# M222B.net
KiCad netlist of a schematic drawn in EAGLE
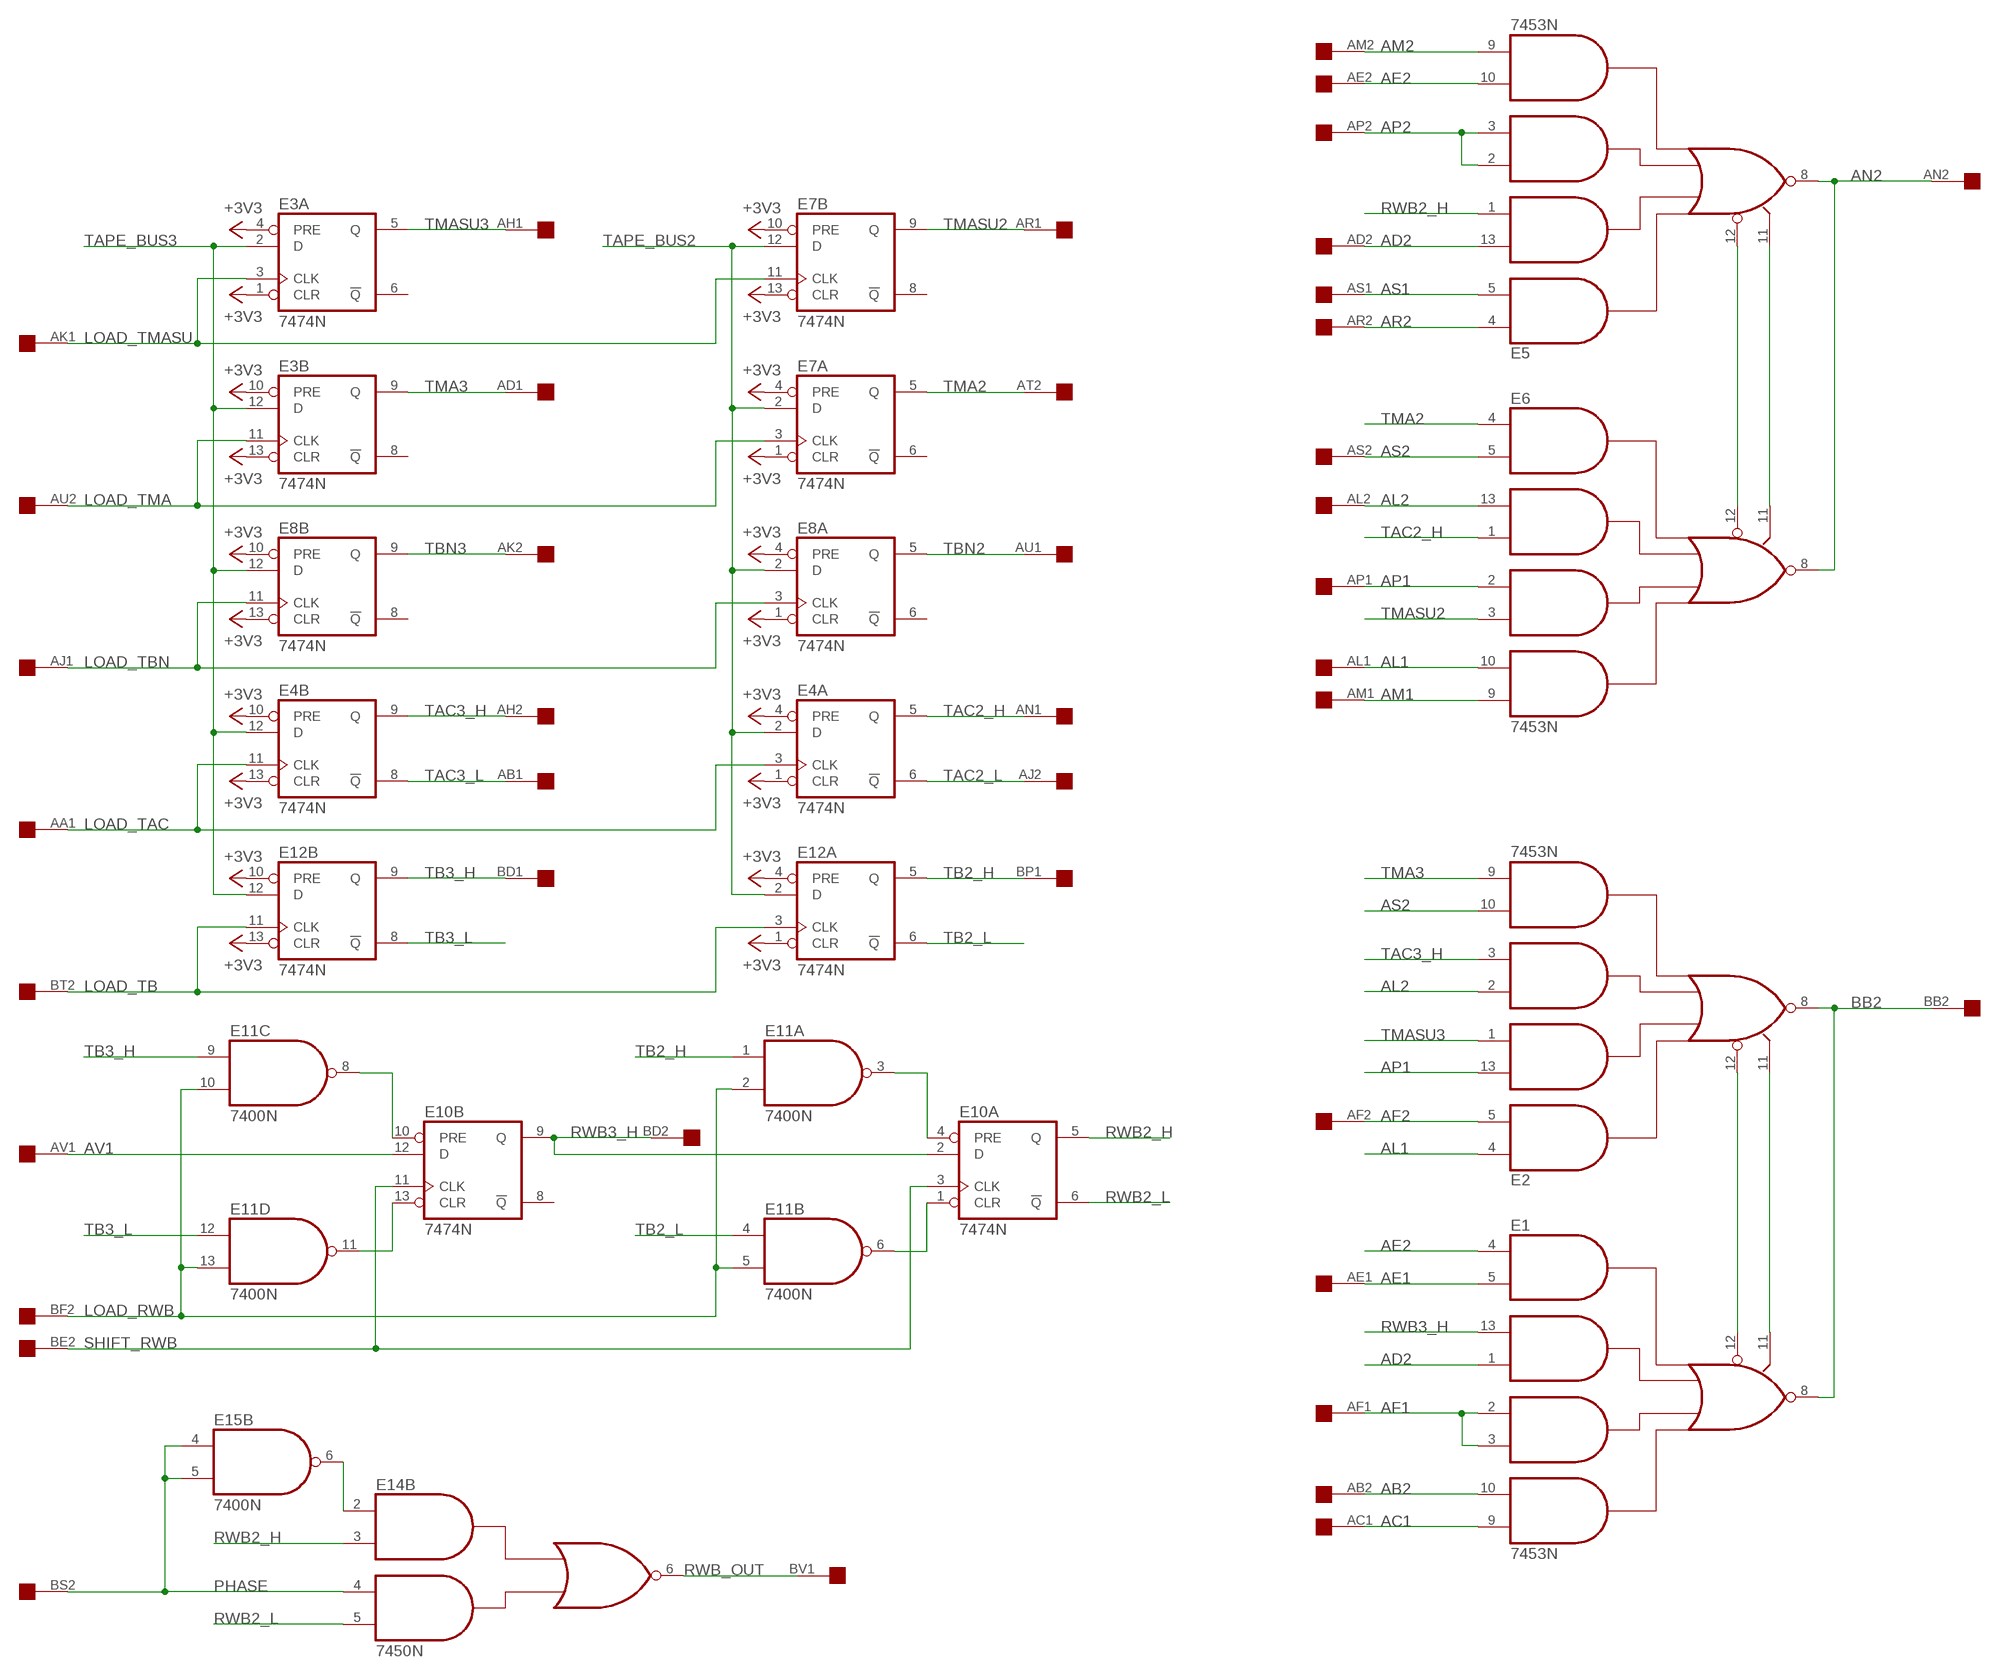
[diagram p0: schematic, sheet 1, part 1 of 2]
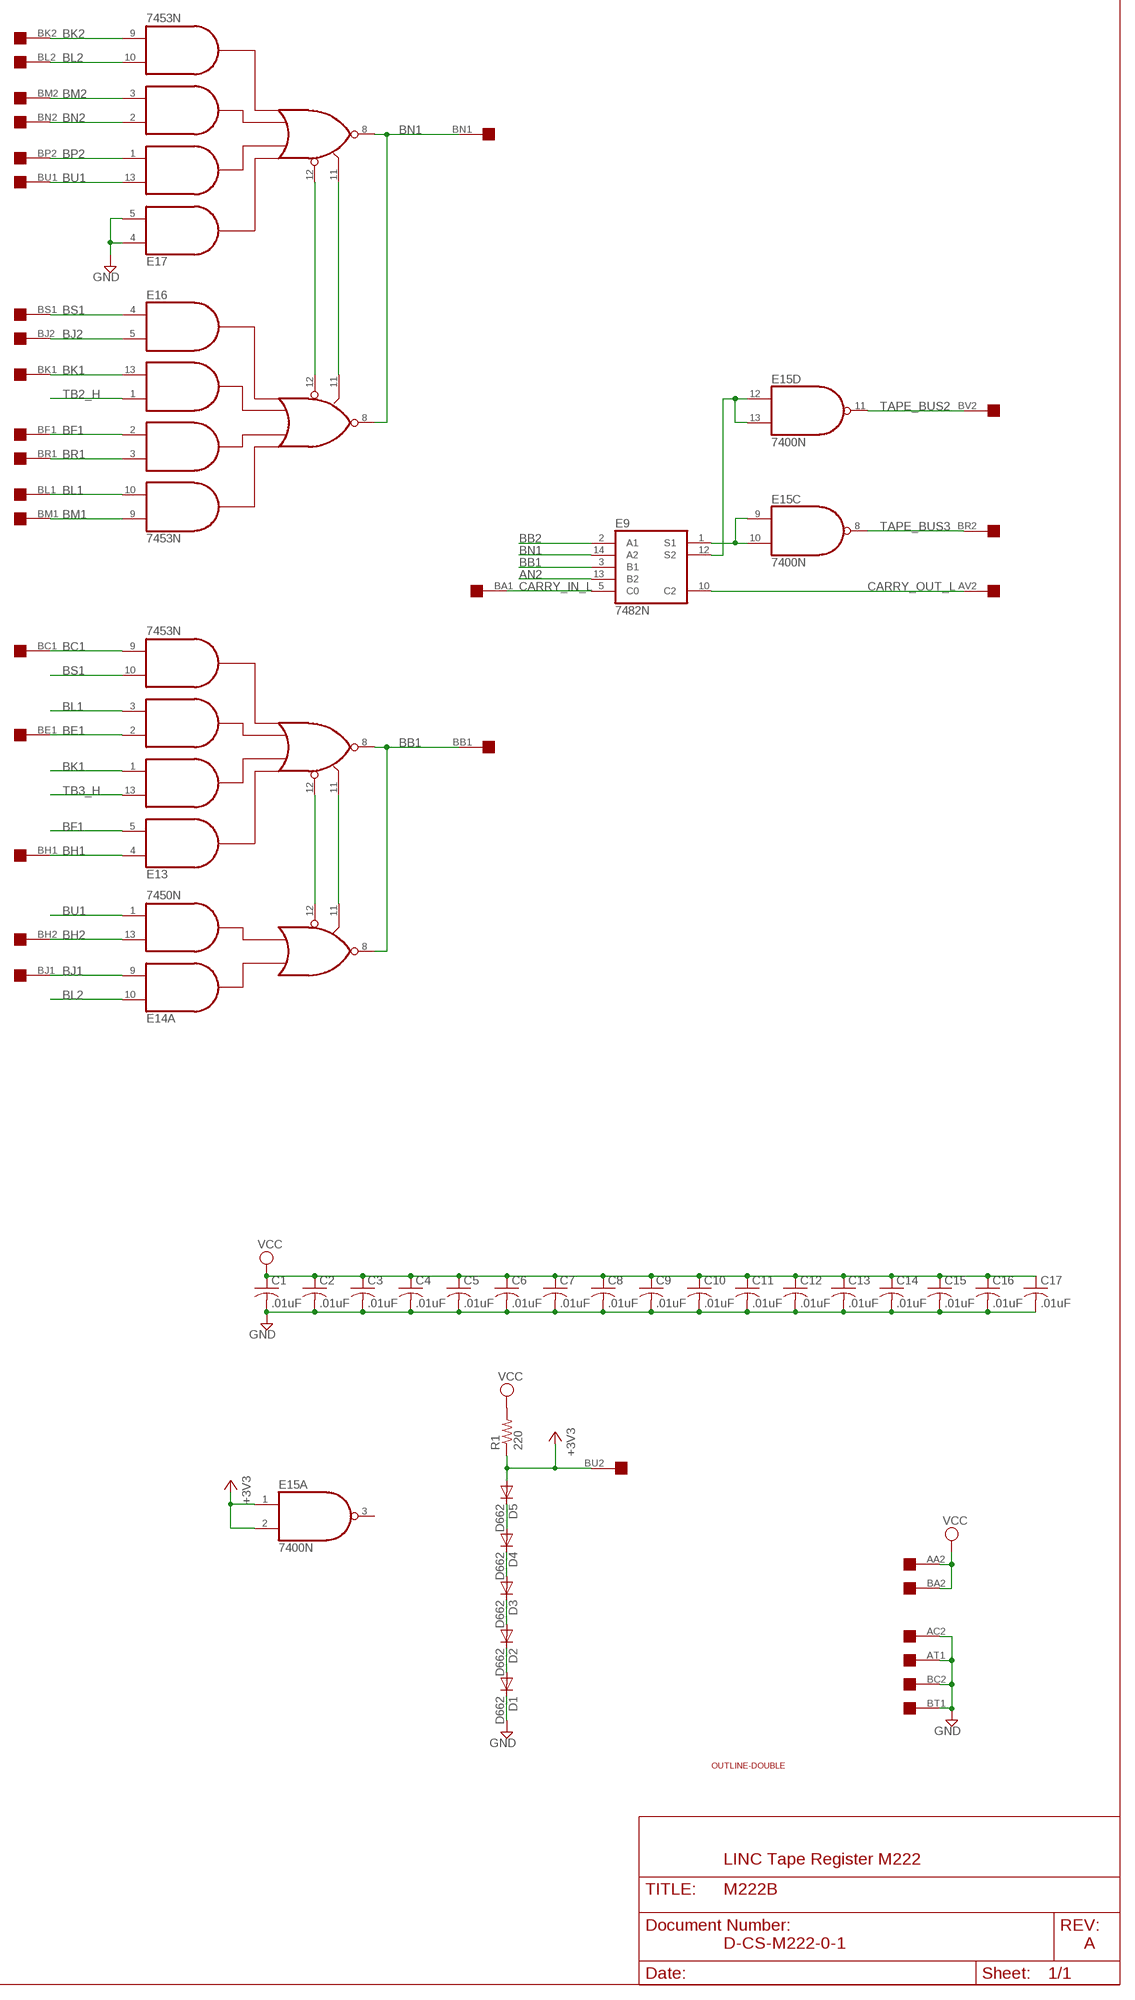
[diagram p1: schematic, sheet 1, part 2 of 2]

(export (version "E")
  (design (tool "Eeschema 10.0.6"))
  (components
    (comp (ref "C1")
      (value ".01uF")
      (footprint "eagle-import:C050-025X075")
      (libsource (lib "eagle-import") (part "C-US050-025X075"))
    )
    (comp (ref "C2")
      (value ".01uF")
      (footprint "eagle-import:C050-025X075")
      (libsource (lib "eagle-import") (part "C-US050-025X075"))
    )
    (comp (ref "C3")
      (value ".01uF")
      (footprint "eagle-import:C050-025X075")
      (libsource (lib "eagle-import") (part "C-US050-025X075"))
    )
    (comp (ref "C4")
      (value ".01uF")
      (footprint "eagle-import:C050-025X075")
      (libsource (lib "eagle-import") (part "C-US050-025X075"))
    )
    (comp (ref "C5")
      (value ".01uF")
      (footprint "eagle-import:C050-025X075")
      (libsource (lib "eagle-import") (part "C-US050-025X075"))
    )
    (comp (ref "C6")
      (value ".01uF")
      (footprint "eagle-import:C050-025X075")
      (libsource (lib "eagle-import") (part "C-US050-025X075"))
    )
    (comp (ref "C7")
      (value ".01uF")
      (footprint "eagle-import:C050-025X075")
      (libsource (lib "eagle-import") (part "C-US050-025X075"))
    )
    (comp (ref "C8")
      (value ".01uF")
      (footprint "eagle-import:C050-025X075")
      (libsource (lib "eagle-import") (part "C-US050-025X075"))
    )
    (comp (ref "C9")
      (value ".01uF")
      (footprint "eagle-import:C050-025X075")
      (libsource (lib "eagle-import") (part "C-US050-025X075"))
    )
    (comp (ref "C10")
      (value ".01uF")
      (footprint "eagle-import:C050-025X075")
      (libsource (lib "eagle-import") (part "C-US050-025X075"))
    )
    (comp (ref "C11")
      (value ".01uF")
      (footprint "eagle-import:C050-025X075")
      (libsource (lib "eagle-import") (part "C-US050-025X075"))
    )
    (comp (ref "C12")
      (value ".01uF")
      (footprint "eagle-import:C050-025X075")
      (libsource (lib "eagle-import") (part "C-US050-025X075"))
    )
    (comp (ref "C13")
      (value ".01uF")
      (footprint "eagle-import:C050-025X075")
      (libsource (lib "eagle-import") (part "C-US050-025X075"))
    )
    (comp (ref "C14")
      (value ".01uF")
      (footprint "eagle-import:C050-025X075")
      (libsource (lib "eagle-import") (part "C-US050-025X075"))
    )
    (comp (ref "C15")
      (value ".01uF")
      (footprint "eagle-import:C050-025X075")
      (libsource (lib "eagle-import") (part "C-US050-025X075"))
    )
    (comp (ref "C16")
      (value ".01uF")
      (footprint "eagle-import:C050-025X075")
      (libsource (lib "eagle-import") (part "C-US050-025X075"))
    )
    (comp (ref "C17")
      (value ".01uF")
      (footprint "eagle-import:C050-025X075")
      (libsource (lib "eagle-import") (part "C-US050-025X075"))
    )
    (comp (ref "D1")
      (value "D662")
      (footprint "eagle-import:DO35-10")
      (libsource (lib "eagle-import") (part "1N4148DO35-10"))
    )
    (comp (ref "D2")
      (value "D662")
      (footprint "eagle-import:DO35-10")
      (libsource (lib "eagle-import") (part "1N4148DO35-10"))
    )
    (comp (ref "D3")
      (value "D662")
      (footprint "eagle-import:DO35-10")
      (libsource (lib "eagle-import") (part "1N4148DO35-10"))
    )
    (comp (ref "D4")
      (value "D662")
      (footprint "eagle-import:DO35-10")
      (libsource (lib "eagle-import") (part "1N4148DO35-10"))
    )
    (comp (ref "D5")
      (value "D662")
      (footprint "eagle-import:DO35-10")
      (libsource (lib "eagle-import") (part "1N4148DO35-10"))
    )
    (comp (ref "E1")
      (value "7453N")
      (footprint "eagle-import:DIL14")
      (libsource (lib "eagle-import") (part "7453N"))
    )
    (comp (ref "E2")
      (value "7453N")
      (footprint "eagle-import:DIL14")
      (libsource (lib "eagle-import") (part "7453N"))
    )
    (comp (ref "E3")
      (value "7474N")
      (footprint "eagle-import:DIL14")
      (libsource (lib "eagle-import") (part "7474NS"))
    )
    (comp (ref "E4")
      (value "7474N")
      (footprint "eagle-import:DIL14")
      (libsource (lib "eagle-import") (part "7474NS"))
    )
    (comp (ref "E5")
      (value "7453N")
      (footprint "eagle-import:DIL14")
      (libsource (lib "eagle-import") (part "7453N"))
    )
    (comp (ref "E6")
      (value "7453N")
      (footprint "eagle-import:DIL14")
      (libsource (lib "eagle-import") (part "7453N"))
    )
    (comp (ref "E7")
      (value "7474N")
      (footprint "eagle-import:DIL14")
      (libsource (lib "eagle-import") (part "7474NS"))
    )
    (comp (ref "E8")
      (value "7474N")
      (footprint "eagle-import:DIL14")
      (libsource (lib "eagle-import") (part "7474NS"))
    )
    (comp (ref "E9")
      (value "7482N")
      (footprint "eagle-import:DIL14")
      (libsource (lib "eagle-import") (part "7482N"))
    )
    (comp (ref "E10")
      (value "7474N")
      (footprint "eagle-import:DIL14")
      (libsource (lib "eagle-import") (part "7474NS"))
    )
    (comp (ref "E11")
      (value "7400N")
      (footprint "eagle-import:DIL14")
      (libsource (lib "eagle-import") (part "7400N"))
    )
    (comp (ref "E12")
      (value "7474N")
      (footprint "eagle-import:DIL14")
      (libsource (lib "eagle-import") (part "7474NS"))
    )
    (comp (ref "E13")
      (value "7453N")
      (footprint "eagle-import:DIL14")
      (libsource (lib "eagle-import") (part "7453N"))
    )
    (comp (ref "E14")
      (value "7450N")
      (footprint "eagle-import:DIL14")
      (libsource (lib "eagle-import") (part "7450N"))
    )
    (comp (ref "E15")
      (value "7400N")
      (footprint "eagle-import:DIL14")
      (libsource (lib "eagle-import") (part "7400N"))
    )
    (comp (ref "E16")
      (value "7453N")
      (footprint "eagle-import:DIL14")
      (libsource (lib "eagle-import") (part "7453N"))
    )
    (comp (ref "E17")
      (value "7453N")
      (footprint "eagle-import:DIL14")
      (libsource (lib "eagle-import") (part "7453N"))
    )
    (comp (ref "R1")
      (value "220")
      (footprint "eagle-import:0207_10")
      (libsource (lib "eagle-import") (part "R-US_0207/10"))
    )
    (comp (ref "U$1")
      (value "DOUBLE")
      (footprint "eagle-import:EDGE-CON4")
      (libsource (lib "eagle-import") (part "DOUBLE"))
    )
    (comp (ref "U$2")
      (value "OUTLINE-DOUBLE")
      (footprint "eagle-import:DOUBLE")
      (libsource (lib "eagle-import") (part "OUTLINE-DOUBLE"))
    )
  )
  (nets
    (net (code "1") (name "+3V3") (class "Default")
      (node (ref "D5") (pin "A") (pinfunction "A_A") (pintype "passive"))
      (node (ref "E12") (pin "1") (pinfunction "CLR_1") (pintype "input"))
      (node (ref "E12") (pin "10") (pinfunction "PRE_10") (pintype "input"))
      (node (ref "E12") (pin "13") (pinfunction "CLR_13") (pintype "input"))
      (node (ref "E12") (pin "4") (pinfunction "PRE_4") (pintype "input"))
      (node (ref "E15") (pin "1") (pinfunction "I0_1") (pintype "input"))
      (node (ref "E15") (pin "2") (pinfunction "I1_2") (pintype "input"))
      (node (ref "E3") (pin "1") (pinfunction "CLR_1") (pintype "input"))
      (node (ref "E3") (pin "10") (pinfunction "PRE_10") (pintype "input"))
      (node (ref "E3") (pin "13") (pinfunction "CLR_13") (pintype "input"))
      (node (ref "E3") (pin "4") (pinfunction "PRE_4") (pintype "input"))
      (node (ref "E4") (pin "1") (pinfunction "CLR_1") (pintype "input"))
      (node (ref "E4") (pin "10") (pinfunction "PRE_10") (pintype "input"))
      (node (ref "E4") (pin "13") (pinfunction "CLR_13") (pintype "input"))
      (node (ref "E4") (pin "4") (pinfunction "PRE_4") (pintype "input"))
      (node (ref "E7") (pin "1") (pinfunction "CLR_1") (pintype "input"))
      (node (ref "E7") (pin "10") (pinfunction "PRE_10") (pintype "input"))
      (node (ref "E7") (pin "13") (pinfunction "CLR_13") (pintype "input"))
      (node (ref "E7") (pin "4") (pinfunction "PRE_4") (pintype "input"))
      (node (ref "E8") (pin "1") (pinfunction "CLR_1") (pintype "input"))
      (node (ref "E8") (pin "10") (pinfunction "PRE_10") (pintype "input"))
      (node (ref "E8") (pin "13") (pinfunction "CLR_13") (pintype "input"))
      (node (ref "E8") (pin "4") (pinfunction "PRE_4") (pintype "input"))
      (node (ref "R1") (pin "1") (pinfunction "1_1") (pintype "passive"))
      (node (ref "U$1") (pin "BU2") (pinfunction "1_BU2") (pintype "bidirectional"))
    )
    (net (code "2") (name "/AB2") (class "Default")
      (node (ref "E1") (pin "10") (pinfunction "I7_10") (pintype "input"))
      (node (ref "U$1") (pin "AB2") (pinfunction "1_AB2") (pintype "bidirectional"))
    )
    (net (code "3") (name "/AC1") (class "Default")
      (node (ref "E1") (pin "9") (pinfunction "I8_9") (pintype "input"))
      (node (ref "U$1") (pin "AC1") (pinfunction "1_AC1") (pintype "bidirectional"))
    )
    (net (code "4") (name "/AD2") (class "Default")
      (node (ref "E1") (pin "1") (pinfunction "I4_1") (pintype "input"))
      (node (ref "E5") (pin "13") (pinfunction "I3_13") (pintype "input"))
      (node (ref "U$1") (pin "AD2") (pinfunction "1_AD2") (pintype "bidirectional"))
    )
    (net (code "5") (name "/AE1") (class "Default")
      (node (ref "E1") (pin "5") (pinfunction "I2_5") (pintype "input"))
      (node (ref "U$1") (pin "AE1") (pinfunction "1_AE1") (pintype "bidirectional"))
    )
    (net (code "6") (name "/AE2") (class "Default")
      (node (ref "E1") (pin "4") (pinfunction "I1_4") (pintype "input"))
      (node (ref "E5") (pin "10") (pinfunction "I7_10") (pintype "input"))
      (node (ref "U$1") (pin "AE2") (pinfunction "1_AE2") (pintype "bidirectional"))
    )
    (net (code "7") (name "/AF1") (class "Default")
      (node (ref "E1") (pin "2") (pinfunction "I5_2") (pintype "input"))
      (node (ref "E1") (pin "3") (pinfunction "I6_3") (pintype "input"))
      (node (ref "U$1") (pin "AF1") (pinfunction "1_AF1") (pintype "bidirectional"))
    )
    (net (code "8") (name "/AF2") (class "Default")
      (node (ref "E2") (pin "5") (pinfunction "I2_5") (pintype "input"))
      (node (ref "U$1") (pin "AF2") (pinfunction "1_AF2") (pintype "bidirectional"))
    )
    (net (code "9") (name "/AL1") (class "Default")
      (node (ref "E2") (pin "4") (pinfunction "I1_4") (pintype "input"))
      (node (ref "E6") (pin "10") (pinfunction "I7_10") (pintype "input"))
      (node (ref "U$1") (pin "AL1") (pinfunction "1_AL1") (pintype "bidirectional"))
    )
    (net (code "10") (name "/AL2") (class "Default")
      (node (ref "E2") (pin "2") (pinfunction "I5_2") (pintype "input"))
      (node (ref "E6") (pin "13") (pinfunction "I3_13") (pintype "input"))
      (node (ref "U$1") (pin "AL2") (pinfunction "1_AL2") (pintype "bidirectional"))
    )
    (net (code "11") (name "/AM1") (class "Default")
      (node (ref "E6") (pin "9") (pinfunction "I8_9") (pintype "input"))
      (node (ref "U$1") (pin "AM1") (pinfunction "1_AM1") (pintype "bidirectional"))
    )
    (net (code "12") (name "/AM2") (class "Default")
      (node (ref "E5") (pin "9") (pinfunction "I8_9") (pintype "input"))
      (node (ref "U$1") (pin "AM2") (pinfunction "1_AM2") (pintype "bidirectional"))
    )
    (net (code "13") (name "/AN2") (class "Default")
      (node (ref "E5") (pin "8") (pinfunction "O_8") (pintype "output"))
      (node (ref "E6") (pin "8") (pinfunction "O_8") (pintype "output"))
      (node (ref "E9") (pin "13") (pinfunction "B2_13") (pintype "input"))
      (node (ref "U$1") (pin "AN2") (pinfunction "1_AN2") (pintype "bidirectional"))
    )
    (net (code "14") (name "/AP1") (class "Default")
      (node (ref "E2") (pin "13") (pinfunction "I3_13") (pintype "input"))
      (node (ref "E6") (pin "2") (pinfunction "I5_2") (pintype "input"))
      (node (ref "U$1") (pin "AP1") (pinfunction "1_AP1") (pintype "bidirectional"))
    )
    (net (code "15") (name "/AP2") (class "Default")
      (node (ref "E5") (pin "2") (pinfunction "I5_2") (pintype "input"))
      (node (ref "E5") (pin "3") (pinfunction "I6_3") (pintype "input"))
      (node (ref "U$1") (pin "AP2") (pinfunction "1_AP2") (pintype "bidirectional"))
    )
    (net (code "16") (name "/AR2") (class "Default")
      (node (ref "E5") (pin "4") (pinfunction "I1_4") (pintype "input"))
      (node (ref "U$1") (pin "AR2") (pinfunction "1_AR2") (pintype "bidirectional"))
    )
    (net (code "17") (name "/AS1") (class "Default")
      (node (ref "E5") (pin "5") (pinfunction "I2_5") (pintype "input"))
      (node (ref "U$1") (pin "AS1") (pinfunction "1_AS1") (pintype "bidirectional"))
    )
    (net (code "18") (name "/AS2") (class "Default")
      (node (ref "E2") (pin "10") (pinfunction "I7_10") (pintype "input"))
      (node (ref "E6") (pin "5") (pinfunction "I2_5") (pintype "input"))
      (node (ref "U$1") (pin "AS2") (pinfunction "1_AS2") (pintype "bidirectional"))
    )
    (net (code "19") (name "/AV1") (class "Default")
      (node (ref "E10") (pin "12") (pinfunction "D_12") (pintype "input"))
      (node (ref "U$1") (pin "AV1") (pinfunction "1_AV1") (pintype "bidirectional"))
    )
    (net (code "20") (name "/BB1") (class "Default")
      (node (ref "E13") (pin "8") (pinfunction "O_8") (pintype "output"))
      (node (ref "E14") (pin "8") (pinfunction "O_8") (pintype "output"))
      (node (ref "E9") (pin "3") (pinfunction "B1_3") (pintype "input"))
      (node (ref "U$1") (pin "BB1") (pinfunction "1_BB1") (pintype "bidirectional"))
    )
    (net (code "21") (name "/BB2") (class "Default")
      (node (ref "E1") (pin "8") (pinfunction "O_8") (pintype "output"))
      (node (ref "E2") (pin "8") (pinfunction "O_8") (pintype "output"))
      (node (ref "E9") (pin "2") (pinfunction "A1_2") (pintype "input"))
      (node (ref "U$1") (pin "BB2") (pinfunction "1_BB2") (pintype "bidirectional"))
    )
    (net (code "22") (name "/BC1") (class "Default")
      (node (ref "E13") (pin "9") (pinfunction "I8_9") (pintype "input"))
      (node (ref "U$1") (pin "BC1") (pinfunction "1_BC1") (pintype "bidirectional"))
    )
    (net (code "23") (name "/BE1") (class "Default")
      (node (ref "E13") (pin "2") (pinfunction "I5_2") (pintype "input"))
      (node (ref "U$1") (pin "BE1") (pinfunction "1_BE1") (pintype "bidirectional"))
    )
    (net (code "24") (name "/BF1") (class "Default")
      (node (ref "E13") (pin "5") (pinfunction "I2_5") (pintype "input"))
      (node (ref "E16") (pin "2") (pinfunction "I5_2") (pintype "input"))
      (node (ref "U$1") (pin "BF1") (pinfunction "1_BF1") (pintype "bidirectional"))
    )
    (net (code "25") (name "/BH1") (class "Default")
      (node (ref "E13") (pin "4") (pinfunction "I1_4") (pintype "input"))
      (node (ref "U$1") (pin "BH1") (pinfunction "1_BH1") (pintype "bidirectional"))
    )
    (net (code "26") (name "/BH2") (class "Default")
      (node (ref "E14") (pin "13") (pinfunction "I3_13") (pintype "input"))
      (node (ref "U$1") (pin "BH2") (pinfunction "1_BH2") (pintype "bidirectional"))
    )
    (net (code "27") (name "/BJ1") (class "Default")
      (node (ref "E14") (pin "9") (pinfunction "I2_9") (pintype "input"))
      (node (ref "U$1") (pin "BJ1") (pinfunction "1_BJ1") (pintype "bidirectional"))
    )
    (net (code "28") (name "/BJ2") (class "Default")
      (node (ref "E16") (pin "5") (pinfunction "I2_5") (pintype "input"))
      (node (ref "U$1") (pin "BJ2") (pinfunction "1_BJ2") (pintype "bidirectional"))
    )
    (net (code "29") (name "/BK1") (class "Default")
      (node (ref "E13") (pin "1") (pinfunction "I4_1") (pintype "input"))
      (node (ref "E16") (pin "13") (pinfunction "I3_13") (pintype "input"))
      (node (ref "U$1") (pin "BK1") (pinfunction "1_BK1") (pintype "bidirectional"))
    )
    (net (code "30") (name "/BK2") (class "Default")
      (node (ref "E17") (pin "9") (pinfunction "I8_9") (pintype "input"))
      (node (ref "U$1") (pin "BK2") (pinfunction "1_BK2") (pintype "bidirectional"))
    )
    (net (code "31") (name "/BL1") (class "Default")
      (node (ref "E13") (pin "3") (pinfunction "I6_3") (pintype "input"))
      (node (ref "E16") (pin "10") (pinfunction "I7_10") (pintype "input"))
      (node (ref "U$1") (pin "BL1") (pinfunction "1_BL1") (pintype "bidirectional"))
    )
    (net (code "32") (name "/BL2") (class "Default")
      (node (ref "E14") (pin "10") (pinfunction "I1_10") (pintype "input"))
      (node (ref "E17") (pin "10") (pinfunction "I7_10") (pintype "input"))
      (node (ref "U$1") (pin "BL2") (pinfunction "1_BL2") (pintype "bidirectional"))
    )
    (net (code "33") (name "/BM1") (class "Default")
      (node (ref "E16") (pin "9") (pinfunction "I8_9") (pintype "input"))
      (node (ref "U$1") (pin "BM1") (pinfunction "1_BM1") (pintype "bidirectional"))
    )
    (net (code "34") (name "/BM2") (class "Default")
      (node (ref "E17") (pin "3") (pinfunction "I6_3") (pintype "input"))
      (node (ref "U$1") (pin "BM2") (pinfunction "1_BM2") (pintype "bidirectional"))
    )
    (net (code "35") (name "/BN1") (class "Default")
      (node (ref "E16") (pin "8") (pinfunction "O_8") (pintype "output"))
      (node (ref "E17") (pin "8") (pinfunction "O_8") (pintype "output"))
      (node (ref "E9") (pin "14") (pinfunction "A2_14") (pintype "input"))
      (node (ref "U$1") (pin "BN1") (pinfunction "1_BN1") (pintype "bidirectional"))
    )
    (net (code "36") (name "/BN2") (class "Default")
      (node (ref "E17") (pin "2") (pinfunction "I5_2") (pintype "input"))
      (node (ref "U$1") (pin "BN2") (pinfunction "1_BN2") (pintype "bidirectional"))
    )
    (net (code "37") (name "/BP2") (class "Default")
      (node (ref "E17") (pin "1") (pinfunction "I4_1") (pintype "input"))
      (node (ref "U$1") (pin "BP2") (pinfunction "1_BP2") (pintype "bidirectional"))
    )
    (net (code "38") (name "/BR1") (class "Default")
      (node (ref "E16") (pin "3") (pinfunction "I6_3") (pintype "input"))
      (node (ref "U$1") (pin "BR1") (pinfunction "1_BR1") (pintype "bidirectional"))
    )
    (net (code "39") (name "/BS1") (class "Default")
      (node (ref "E13") (pin "10") (pinfunction "I7_10") (pintype "input"))
      (node (ref "E16") (pin "4") (pinfunction "I1_4") (pintype "input"))
      (node (ref "U$1") (pin "BS1") (pinfunction "1_BS1") (pintype "bidirectional"))
    )
    (net (code "40") (name "/BU1") (class "Default")
      (node (ref "E14") (pin "1") (pinfunction "I4_1") (pintype "input"))
      (node (ref "E17") (pin "13") (pinfunction "I3_13") (pintype "input"))
      (node (ref "U$1") (pin "BU1") (pinfunction "1_BU1") (pintype "bidirectional"))
    )
    (net (code "41") (name "/CARRY_IN_L") (class "Default")
      (node (ref "E9") (pin "5") (pinfunction "C0_5") (pintype "input"))
      (node (ref "U$1") (pin "BA1") (pinfunction "1_BA1") (pintype "bidirectional"))
    )
    (net (code "42") (name "/CARRY_OUT_L") (class "Default")
      (node (ref "E9") (pin "10") (pinfunction "C2_10") (pintype "output"))
      (node (ref "U$1") (pin "AV2") (pinfunction "1_AV2") (pintype "bidirectional"))
    )
    (net (code "43") (name "/LOAD_RWB") (class "Default")
      (node (ref "E11") (pin "10") (pinfunction "I1_10") (pintype "input"))
      (node (ref "E11") (pin "13") (pinfunction "I1_13") (pintype "input"))
      (node (ref "E11") (pin "2") (pinfunction "I1_2") (pintype "input"))
      (node (ref "E11") (pin "5") (pinfunction "I1_5") (pintype "input"))
      (node (ref "U$1") (pin "BF2") (pinfunction "1_BF2") (pintype "bidirectional"))
    )
    (net (code "44") (name "/LOAD_TAC") (class "Default")
      (node (ref "E4") (pin "11") (pinfunction "CLK_11") (pintype "input"))
      (node (ref "E4") (pin "3") (pinfunction "CLK_3") (pintype "input"))
      (node (ref "U$1") (pin "AA1") (pinfunction "1_AA1") (pintype "bidirectional"))
    )
    (net (code "45") (name "/LOAD_TB") (class "Default")
      (node (ref "E12") (pin "11") (pinfunction "CLK_11") (pintype "input"))
      (node (ref "E12") (pin "3") (pinfunction "CLK_3") (pintype "input"))
      (node (ref "U$1") (pin "BT2") (pinfunction "1_BT2") (pintype "bidirectional"))
    )
    (net (code "46") (name "/LOAD_TBN") (class "Default")
      (node (ref "E8") (pin "11") (pinfunction "CLK_11") (pintype "input"))
      (node (ref "E8") (pin "3") (pinfunction "CLK_3") (pintype "input"))
      (node (ref "U$1") (pin "AJ1") (pinfunction "1_AJ1") (pintype "bidirectional"))
    )
    (net (code "47") (name "/LOAD_TMA") (class "Default")
      (node (ref "E3") (pin "11") (pinfunction "CLK_11") (pintype "input"))
      (node (ref "E7") (pin "3") (pinfunction "CLK_3") (pintype "input"))
      (node (ref "U$1") (pin "AU2") (pinfunction "1_AU2") (pintype "bidirectional"))
    )
    (net (code "48") (name "/LOAD_TMASU") (class "Default")
      (node (ref "E3") (pin "3") (pinfunction "CLK_3") (pintype "input"))
      (node (ref "E7") (pin "11") (pinfunction "CLK_11") (pintype "input"))
      (node (ref "U$1") (pin "AK1") (pinfunction "1_AK1") (pintype "bidirectional"))
    )
    (net (code "49") (name "/PHASE") (class "Default")
      (node (ref "E14") (pin "4") (pinfunction "I3_4") (pintype "input"))
      (node (ref "E15") (pin "4") (pinfunction "I0_4") (pintype "input"))
      (node (ref "E15") (pin "5") (pinfunction "I1_5") (pintype "input"))
      (node (ref "U$1") (pin "BS2") (pinfunction "1_BS2") (pintype "bidirectional"))
    )
    (net (code "50") (name "/RWB2_H") (class "Default")
      (node (ref "E10") (pin "5") (pinfunction "Q_5") (pintype "output"))
      (node (ref "E14") (pin "3") (pinfunction "I2_3") (pintype "input"))
      (node (ref "E5") (pin "1") (pinfunction "I4_1") (pintype "input"))
    )
    (net (code "51") (name "/RWB2_L") (class "Default")
      (node (ref "E10") (pin "6") (pinfunction "~{Q}_6") (pintype "output"))
      (node (ref "E14") (pin "5") (pinfunction "I4_5") (pintype "input"))
    )
    (net (code "52") (name "/RWB3_H") (class "Default")
      (node (ref "E1") (pin "13") (pinfunction "I3_13") (pintype "input"))
      (node (ref "E10") (pin "2") (pinfunction "D_2") (pintype "input"))
      (node (ref "E10") (pin "9") (pinfunction "Q_9") (pintype "output"))
      (node (ref "U$1") (pin "BD2") (pinfunction "1_BD2") (pintype "bidirectional"))
    )
    (net (code "53") (name "/RWB_OUT") (class "Default")
      (node (ref "E14") (pin "6") (pinfunction "O_6") (pintype "output"))
      (node (ref "U$1") (pin "BV1") (pinfunction "1_BV1") (pintype "bidirectional"))
    )
    (net (code "54") (name "/SHIFT_RWB") (class "Default")
      (node (ref "E10") (pin "11") (pinfunction "CLK_11") (pintype "input"))
      (node (ref "E10") (pin "3") (pinfunction "CLK_3") (pintype "input"))
      (node (ref "U$1") (pin "BE2") (pinfunction "1_BE2") (pintype "bidirectional"))
    )
    (net (code "55") (name "/TAC2_H") (class "Default")
      (node (ref "E4") (pin "5") (pinfunction "Q_5") (pintype "output"))
      (node (ref "E6") (pin "1") (pinfunction "I4_1") (pintype "input"))
      (node (ref "U$1") (pin "AN1") (pinfunction "1_AN1") (pintype "bidirectional"))
    )
    (net (code "56") (name "/TAC2_L") (class "Default")
      (node (ref "E4") (pin "6") (pinfunction "~{Q}_6") (pintype "output"))
      (node (ref "U$1") (pin "AJ2") (pinfunction "1_AJ2") (pintype "bidirectional"))
    )
    (net (code "57") (name "/TAC3_H") (class "Default")
      (node (ref "E2") (pin "3") (pinfunction "I6_3") (pintype "input"))
      (node (ref "E4") (pin "9") (pinfunction "Q_9") (pintype "output"))
      (node (ref "U$1") (pin "AH2") (pinfunction "1_AH2") (pintype "bidirectional"))
    )
    (net (code "58") (name "/TAC3_L") (class "Default")
      (node (ref "E4") (pin "8") (pinfunction "~{Q}_8") (pintype "output"))
      (node (ref "U$1") (pin "AB1") (pinfunction "1_AB1") (pintype "bidirectional"))
    )
    (net (code "59") (name "/TAPE_BUS2") (class "Default")
      (node (ref "E12") (pin "2") (pinfunction "D_2") (pintype "input"))
      (node (ref "E15") (pin "11") (pinfunction "O_11") (pintype "output"))
      (node (ref "E4") (pin "2") (pinfunction "D_2") (pintype "input"))
      (node (ref "E7") (pin "12") (pinfunction "D_12") (pintype "input"))
      (node (ref "E7") (pin "2") (pinfunction "D_2") (pintype "input"))
      (node (ref "E8") (pin "2") (pinfunction "D_2") (pintype "input"))
      (node (ref "U$1") (pin "BV2") (pinfunction "1_BV2") (pintype "bidirectional"))
    )
    (net (code "60") (name "/TAPE_BUS3") (class "Default")
      (node (ref "E12") (pin "12") (pinfunction "D_12") (pintype "input"))
      (node (ref "E15") (pin "8") (pinfunction "O_8") (pintype "output"))
      (node (ref "E3") (pin "12") (pinfunction "D_12") (pintype "input"))
      (node (ref "E3") (pin "2") (pinfunction "D_2") (pintype "input"))
      (node (ref "E4") (pin "12") (pinfunction "D_12") (pintype "input"))
      (node (ref "E8") (pin "12") (pinfunction "D_12") (pintype "input"))
      (node (ref "U$1") (pin "BR2") (pinfunction "1_BR2") (pintype "bidirectional"))
    )
    (net (code "61") (name "/TB2_H") (class "Default")
      (node (ref "E11") (pin "1") (pinfunction "I0_1") (pintype "input"))
      (node (ref "E12") (pin "5") (pinfunction "Q_5") (pintype "output"))
      (node (ref "E16") (pin "1") (pinfunction "I4_1") (pintype "input"))
      (node (ref "U$1") (pin "BP1") (pinfunction "1_BP1") (pintype "bidirectional"))
    )
    (net (code "62") (name "/TB2_L") (class "Default")
      (node (ref "E11") (pin "4") (pinfunction "I0_4") (pintype "input"))
      (node (ref "E12") (pin "6") (pinfunction "~{Q}_6") (pintype "output"))
    )
    (net (code "63") (name "/TB3_H") (class "Default")
      (node (ref "E11") (pin "9") (pinfunction "I0_9") (pintype "input"))
      (node (ref "E12") (pin "9") (pinfunction "Q_9") (pintype "output"))
      (node (ref "E13") (pin "13") (pinfunction "I3_13") (pintype "input"))
      (node (ref "U$1") (pin "BD1") (pinfunction "1_BD1") (pintype "bidirectional"))
    )
    (net (code "64") (name "/TB3_L") (class "Default")
      (node (ref "E11") (pin "12") (pinfunction "I0_12") (pintype "input"))
      (node (ref "E12") (pin "8") (pinfunction "~{Q}_8") (pintype "output"))
    )
    (net (code "65") (name "/TBN2") (class "Default")
      (node (ref "E8") (pin "5") (pinfunction "Q_5") (pintype "output"))
      (node (ref "U$1") (pin "AU1") (pinfunction "1_AU1") (pintype "bidirectional"))
    )
    (net (code "66") (name "/TBN3") (class "Default")
      (node (ref "E8") (pin "9") (pinfunction "Q_9") (pintype "output"))
      (node (ref "U$1") (pin "AK2") (pinfunction "1_AK2") (pintype "bidirectional"))
    )
    (net (code "67") (name "/TMA2") (class "Default")
      (node (ref "E6") (pin "4") (pinfunction "I1_4") (pintype "input"))
      (node (ref "E7") (pin "5") (pinfunction "Q_5") (pintype "output"))
      (node (ref "U$1") (pin "AT2") (pinfunction "1_AT2") (pintype "bidirectional"))
    )
    (net (code "68") (name "/TMA3") (class "Default")
      (node (ref "E2") (pin "9") (pinfunction "I8_9") (pintype "input"))
      (node (ref "E3") (pin "9") (pinfunction "Q_9") (pintype "output"))
      (node (ref "U$1") (pin "AD1") (pinfunction "1_AD1") (pintype "bidirectional"))
    )
    (net (code "69") (name "/TMASU2") (class "Default")
      (node (ref "E6") (pin "3") (pinfunction "I6_3") (pintype "input"))
      (node (ref "E7") (pin "9") (pinfunction "Q_9") (pintype "output"))
      (node (ref "U$1") (pin "AR1") (pinfunction "1_AR1") (pintype "bidirectional"))
    )
    (net (code "70") (name "/TMASU3") (class "Default")
      (node (ref "E2") (pin "1") (pinfunction "I4_1") (pintype "input"))
      (node (ref "E3") (pin "5") (pinfunction "Q_5") (pintype "output"))
      (node (ref "U$1") (pin "AH1") (pinfunction "1_AH1") (pintype "bidirectional"))
    )
    (net (code "71") (name "GND") (class "Default")
      (node (ref "C1") (pin "2") (pinfunction "2_2") (pintype "passive"))
      (node (ref "C10") (pin "2") (pinfunction "2_2") (pintype "passive"))
      (node (ref "C11") (pin "2") (pinfunction "2_2") (pintype "passive"))
      (node (ref "C12") (pin "2") (pinfunction "2_2") (pintype "passive"))
      (node (ref "C13") (pin "2") (pinfunction "2_2") (pintype "passive"))
      (node (ref "C14") (pin "2") (pinfunction "2_2") (pintype "passive"))
      (node (ref "C15") (pin "2") (pinfunction "2_2") (pintype "passive"))
      (node (ref "C16") (pin "2") (pinfunction "2_2") (pintype "passive"))
      (node (ref "C17") (pin "2") (pinfunction "2_2") (pintype "passive"))
      (node (ref "C2") (pin "2") (pinfunction "2_2") (pintype "passive"))
      (node (ref "C3") (pin "2") (pinfunction "2_2") (pintype "passive"))
      (node (ref "C4") (pin "2") (pinfunction "2_2") (pintype "passive"))
      (node (ref "C5") (pin "2") (pinfunction "2_2") (pintype "passive"))
      (node (ref "C6") (pin "2") (pinfunction "2_2") (pintype "passive"))
      (node (ref "C7") (pin "2") (pinfunction "2_2") (pintype "passive"))
      (node (ref "C8") (pin "2") (pinfunction "2_2") (pintype "passive"))
      (node (ref "C9") (pin "2") (pinfunction "2_2") (pintype "passive"))
      (node (ref "D1") (pin "C") (pinfunction "C_C") (pintype "passive"))
      (node (ref "E17") (pin "4") (pinfunction "I1_4") (pintype "input"))
      (node (ref "E17") (pin "5") (pinfunction "I2_5") (pintype "input"))
      (node (ref "U$1") (pin "AC2") (pinfunction "1_AC2") (pintype "bidirectional"))
      (node (ref "U$1") (pin "AT1") (pinfunction "1_AT1") (pintype "bidirectional"))
      (node (ref "U$1") (pin "BC2") (pinfunction "1_BC2") (pintype "bidirectional"))
      (node (ref "U$1") (pin "BT1") (pinfunction "1_BT1") (pintype "bidirectional"))
    )
    (net (code "72") (name "Net-(D1-PadA)") (class "Default")
      (node (ref "D1") (pin "A") (pinfunction "A_A") (pintype "passive"))
      (node (ref "D2") (pin "C") (pinfunction "C_C") (pintype "passive"))
    )
    (net (code "73") (name "Net-(D2-PadA)") (class "Default")
      (node (ref "D2") (pin "A") (pinfunction "A_A") (pintype "passive"))
      (node (ref "D3") (pin "C") (pinfunction "C_C") (pintype "passive"))
    )
    (net (code "74") (name "Net-(D3-PadA)") (class "Default")
      (node (ref "D3") (pin "A") (pinfunction "A_A") (pintype "passive"))
      (node (ref "D4") (pin "C") (pinfunction "C_C") (pintype "passive"))
    )
    (net (code "75") (name "Net-(D4-PadA)") (class "Default")
      (node (ref "D4") (pin "A") (pinfunction "A_A") (pintype "passive"))
      (node (ref "D5") (pin "C") (pinfunction "C_C") (pintype "passive"))
    )
    (net (code "76") (name "Net-(E1A-I9)") (class "Default")
      (node (ref "E1") (pin "12") (pinfunction "I9_12") (pintype "passive"))
      (node (ref "E2") (pin "12") (pinfunction "I9_12") (pintype "passive"))
    )
    (net (code "77") (name "Net-(E1A-I10)") (class "Default")
      (node (ref "E1") (pin "11") (pinfunction "I10_11") (pintype "passive"))
      (node (ref "E2") (pin "11") (pinfunction "I10_11") (pintype "passive"))
    )
    (net (code "78") (name "Net-(E5A-I9)") (class "Default")
      (node (ref "E5") (pin "12") (pinfunction "I9_12") (pintype "passive"))
      (node (ref "E6") (pin "12") (pinfunction "I9_12") (pintype "passive"))
    )
    (net (code "79") (name "Net-(E5A-I10)") (class "Default")
      (node (ref "E5") (pin "11") (pinfunction "I10_11") (pintype "passive"))
      (node (ref "E6") (pin "11") (pinfunction "I10_11") (pintype "passive"))
    )
    (net (code "80") (name "Net-(E10A-CLR)") (class "Default")
      (node (ref "E10") (pin "1") (pinfunction "CLR_1") (pintype "input"))
      (node (ref "E11") (pin "6") (pinfunction "O_6") (pintype "output"))
    )
    (net (code "81") (name "Net-(E10A-PRE)") (class "Default")
      (node (ref "E10") (pin "4") (pinfunction "PRE_4") (pintype "input"))
      (node (ref "E11") (pin "3") (pinfunction "O_3") (pintype "output"))
    )
    (net (code "82") (name "Net-(E10B-CLR)") (class "Default")
      (node (ref "E10") (pin "13") (pinfunction "CLR_13") (pintype "input"))
      (node (ref "E11") (pin "11") (pinfunction "O_11") (pintype "output"))
    )
    (net (code "83") (name "Net-(E10B-PRE)") (class "Default")
      (node (ref "E10") (pin "10") (pinfunction "PRE_10") (pintype "input"))
      (node (ref "E11") (pin "8") (pinfunction "O_8") (pintype "output"))
    )
    (net (code "84") (name "Net-(E13A-I9)") (class "Default")
      (node (ref "E13") (pin "12") (pinfunction "I9_12") (pintype "passive"))
      (node (ref "E14") (pin "12") (pinfunction "I5_12") (pintype "passive"))
    )
    (net (code "85") (name "Net-(E13A-I10)") (class "Default")
      (node (ref "E13") (pin "11") (pinfunction "I10_11") (pintype "passive"))
      (node (ref "E14") (pin "11") (pinfunction "I6_11") (pintype "passive"))
    )
    (net (code "86") (name "Net-(E14B-I1)") (class "Default")
      (node (ref "E14") (pin "2") (pinfunction "I1_2") (pintype "input"))
      (node (ref "E15") (pin "6") (pinfunction "O_6") (pintype "output"))
    )
    (net (code "87") (name "Net-(E15C-I0)") (class "Default")
      (node (ref "E15") (pin "10") (pinfunction "I1_10") (pintype "input"))
      (node (ref "E15") (pin "9") (pinfunction "I0_9") (pintype "input"))
      (node (ref "E9") (pin "1") (pinfunction "S1_1") (pintype "output"))
    )
    (net (code "88") (name "Net-(E15D-I0)") (class "Default")
      (node (ref "E15") (pin "12") (pinfunction "I0_12") (pintype "input"))
      (node (ref "E15") (pin "13") (pinfunction "I1_13") (pintype "input"))
      (node (ref "E9") (pin "12") (pinfunction "S2_12") (pintype "output"))
    )
    (net (code "89") (name "Net-(E16A-I9)") (class "Default")
      (node (ref "E16") (pin "12") (pinfunction "I9_12") (pintype "passive"))
      (node (ref "E17") (pin "12") (pinfunction "I9_12") (pintype "passive"))
    )
    (net (code "90") (name "Net-(E16A-I10)") (class "Default")
      (node (ref "E16") (pin "11") (pinfunction "I10_11") (pintype "passive"))
      (node (ref "E17") (pin "11") (pinfunction "I10_11") (pintype "passive"))
    )
    (net (code "91") (name "VCC") (class "Default")
      (node (ref "C1") (pin "1") (pinfunction "1_1") (pintype "passive"))
      (node (ref "C10") (pin "1") (pinfunction "1_1") (pintype "passive"))
      (node (ref "C11") (pin "1") (pinfunction "1_1") (pintype "passive"))
      (node (ref "C12") (pin "1") (pinfunction "1_1") (pintype "passive"))
      (node (ref "C13") (pin "1") (pinfunction "1_1") (pintype "passive"))
      (node (ref "C14") (pin "1") (pinfunction "1_1") (pintype "passive"))
      (node (ref "C15") (pin "1") (pinfunction "1_1") (pintype "passive"))
      (node (ref "C16") (pin "1") (pinfunction "1_1") (pintype "passive"))
      (node (ref "C17") (pin "1") (pinfunction "1_1") (pintype "passive"))
      (node (ref "C2") (pin "1") (pinfunction "1_1") (pintype "passive"))
      (node (ref "C3") (pin "1") (pinfunction "1_1") (pintype "passive"))
      (node (ref "C4") (pin "1") (pinfunction "1_1") (pintype "passive"))
      (node (ref "C5") (pin "1") (pinfunction "1_1") (pintype "passive"))
      (node (ref "C6") (pin "1") (pinfunction "1_1") (pintype "passive"))
      (node (ref "C7") (pin "1") (pinfunction "1_1") (pintype "passive"))
      (node (ref "C8") (pin "1") (pinfunction "1_1") (pintype "passive"))
      (node (ref "C9") (pin "1") (pinfunction "1_1") (pintype "passive"))
      (node (ref "R1") (pin "2") (pinfunction "2_2") (pintype "passive"))
      (node (ref "U$1") (pin "AA2") (pinfunction "1_AA2") (pintype "bidirectional"))
      (node (ref "U$1") (pin "BA2") (pinfunction "1_BA2") (pintype "bidirectional"))
    )
    (net (code "92") (name "unconnected-(E3A-~{Q}-Pad6)") (class "Default")
      (node (ref "E3") (pin "6") (pinfunction "~{Q}_6") (pintype "output"))
    )
    (net (code "93") (name "unconnected-(E3B-~{Q}-Pad8)") (class "Default")
      (node (ref "E3") (pin "8") (pinfunction "~{Q}_8") (pintype "output"))
    )
    (net (code "94") (name "unconnected-(E7A-~{Q}-Pad6)") (class "Default")
      (node (ref "E7") (pin "6") (pinfunction "~{Q}_6") (pintype "output"))
    )
    (net (code "95") (name "unconnected-(E7B-~{Q}-Pad8)") (class "Default")
      (node (ref "E7") (pin "8") (pinfunction "~{Q}_8") (pintype "output"))
    )
    (net (code "96") (name "unconnected-(E8A-~{Q}-Pad6)") (class "Default")
      (node (ref "E8") (pin "6") (pinfunction "~{Q}_6") (pintype "output"))
    )
    (net (code "97") (name "unconnected-(E8B-~{Q}-Pad8)") (class "Default")
      (node (ref "E8") (pin "8") (pinfunction "~{Q}_8") (pintype "output"))
    )
    (net (code "98") (name "unconnected-(E10B-~{Q}-Pad8)") (class "Default")
      (node (ref "E10") (pin "8") (pinfunction "~{Q}_8") (pintype "output"))
    )
    (net (code "99") (name "unconnected-(E15A-O-Pad3)") (class "Default")
      (node (ref "E15") (pin "3") (pinfunction "O_3") (pintype "output"))
    )
  )
)
